# Sheet-watch.net
KiCad netlist of a schematic drawn in Altium Designer
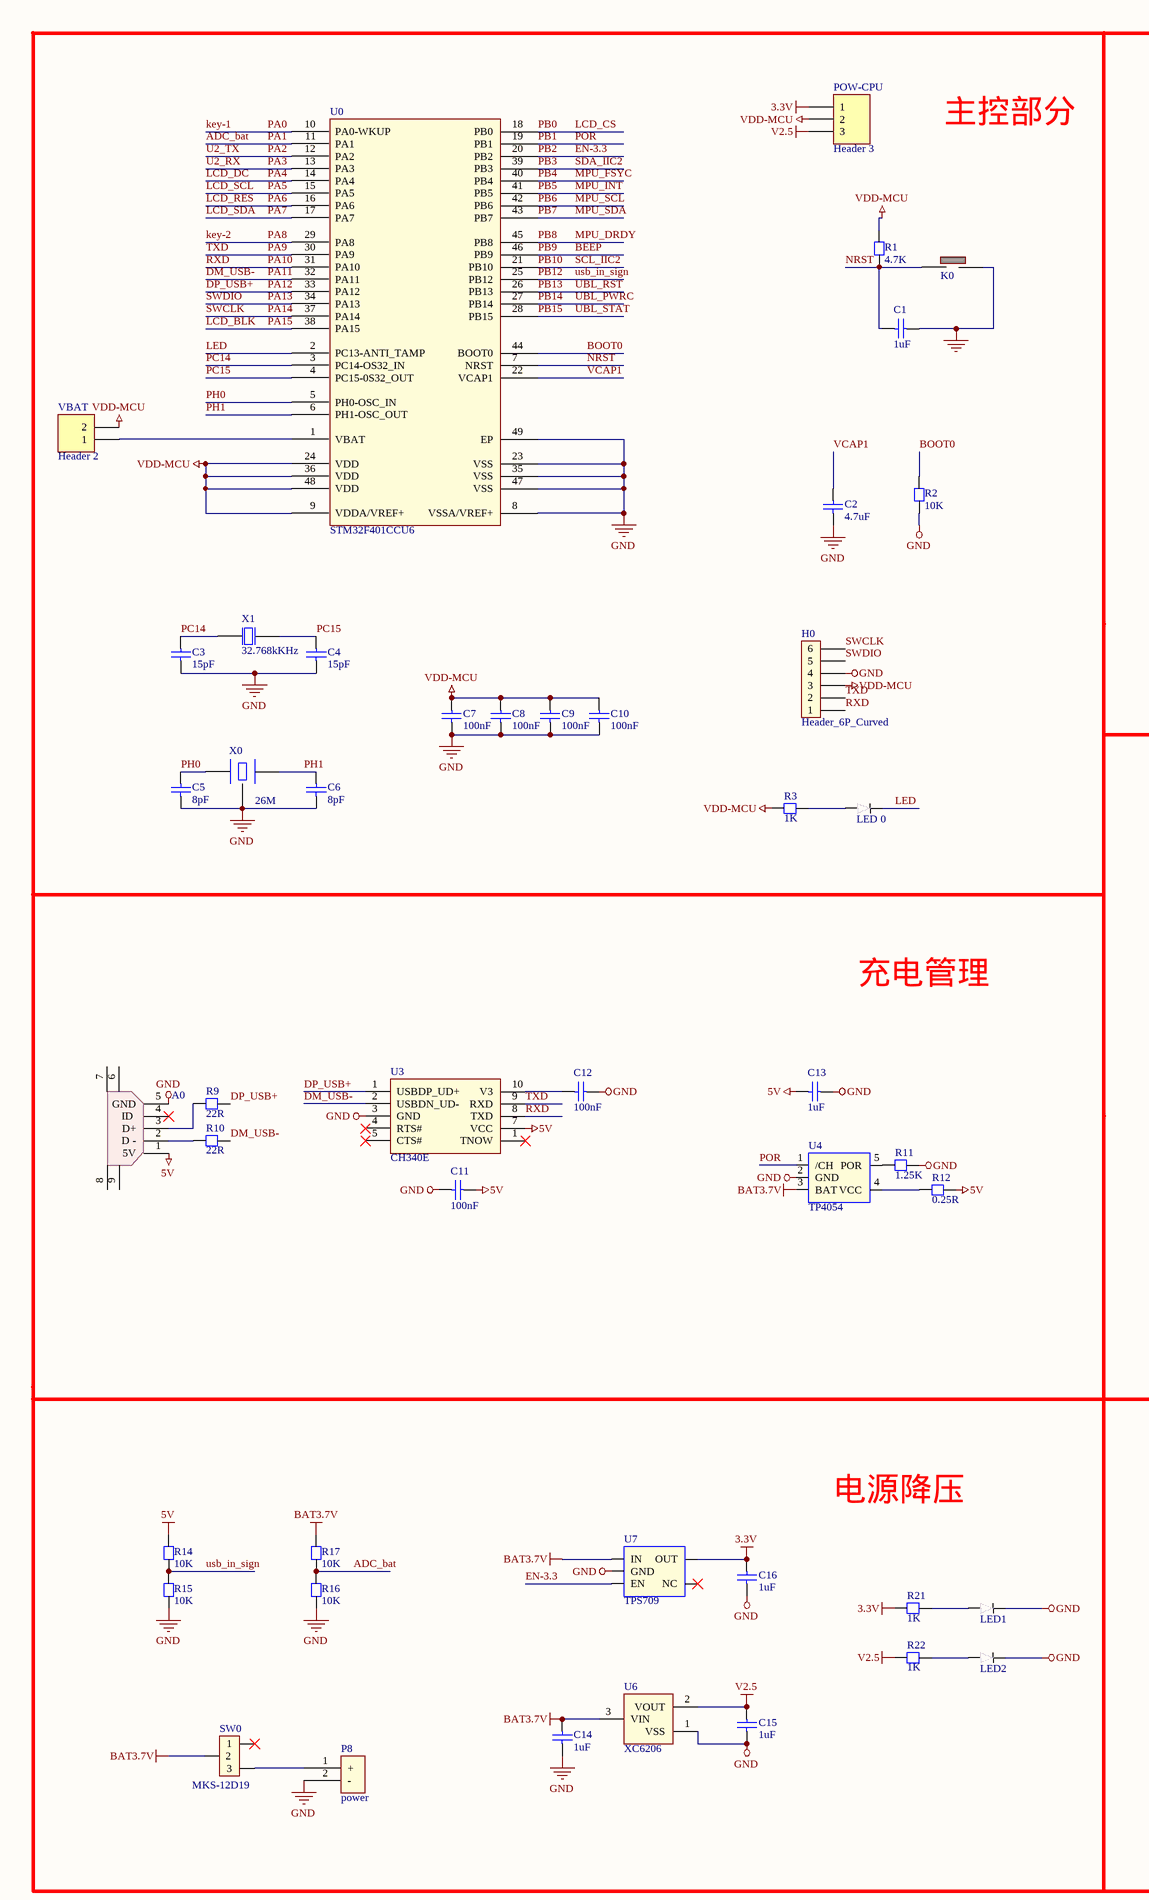
[diagram p0: Sheet-watch.SchDoc, left]
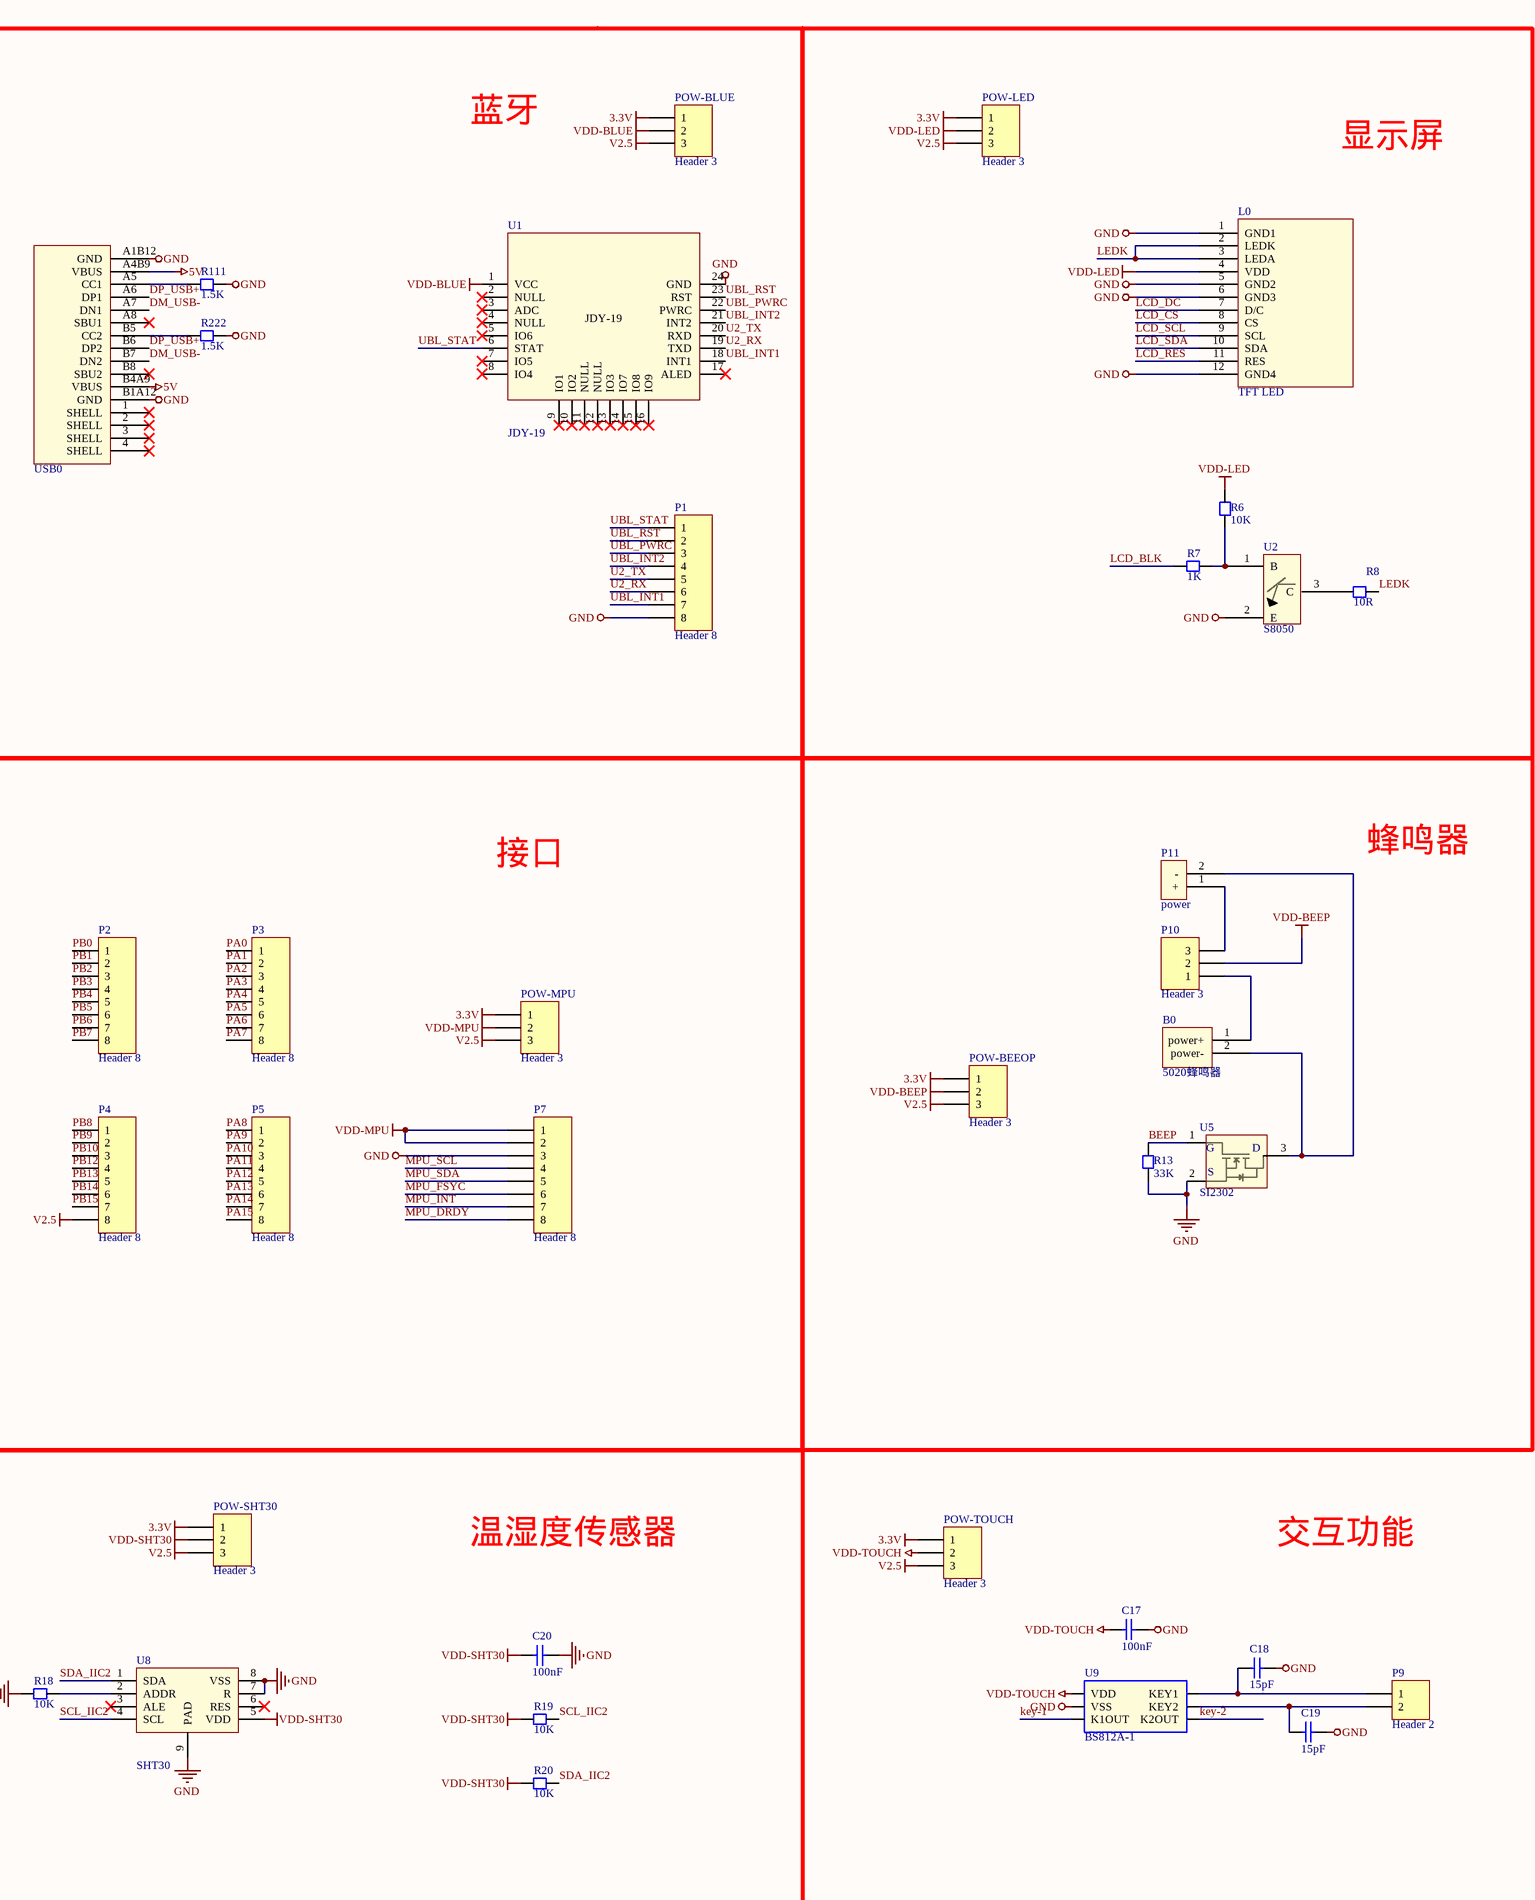
[diagram p1: Sheet-watch.SchDoc, right]

(export (version "E")
  (design (tool "Eeschema 10.0.6"))
  (components
    (comp (ref "A0")
      (value "Micro USB")
      (footprint "Micro usb AB")
      (description "迷你usb接口")
      (libsource (lib "tianxiaohua_Schlib") (part "Micro USB"))
    )
    (comp (ref "B0")
      (value "5020蜂鸣器")
      (footprint "5020蜂鸣器")
      (description "蜂鸣器，贴片封装，长宽5.2mm")
      (libsource (lib "tianxiaohua_Schlib") (part "5020蜂鸣器"))
    )
    (comp (ref "C1")
      (value "1uF")
      (footprint "CC1608-0603")
      (description "电容")
      (fields (field (name "PUBLISHER") "Altium Limited"))
      (libsource (lib "tianxiaohua_Schlib") (part "Cap Chip 0603"))
    )
    (comp (ref "C2")
      (value "4.7uF")
      (footprint "CC1608-0603")
      (description "电容")
      (fields (field (name "PUBLISHER") "Altium Limited"))
      (libsource (lib "tianxiaohua_Schlib") (part "Cap Chip 0603"))
    )
    (comp (ref "C3")
      (value "15pF")
      (footprint "CC1608-0603")
      (description "电容")
      (fields (field (name "PUBLISHER") "Altium Limited"))
      (libsource (lib "tianxiaohua_Schlib") (part "Cap Chip 0603"))
    )
    (comp (ref "C4")
      (value "15pF")
      (footprint "CC1608-0603")
      (description "电容")
      (fields (field (name "PUBLISHER") "Altium Limited"))
      (libsource (lib "tianxiaohua_Schlib") (part "Cap Chip 0603"))
    )
    (comp (ref "C5")
      (value "8pF")
      (footprint "CC1608-0603")
      (description "电容")
      (fields (field (name "PUBLISHER") "Altium Limited"))
      (libsource (lib "tianxiaohua_Schlib") (part "Cap Chip 0603"))
    )
    (comp (ref "C6")
      (value "8pF")
      (footprint "CC1608-0603")
      (description "电容")
      (fields (field (name "PUBLISHER") "Altium Limited"))
      (libsource (lib "tianxiaohua_Schlib") (part "Cap Chip 0603"))
    )
    (comp (ref "C7")
      (value "100nF")
      (footprint "CC1608-0603")
      (description "电容")
      (fields (field (name "PUBLISHER") "Altium Limited"))
      (libsource (lib "tianxiaohua_Schlib") (part "Cap Chip 0603"))
    )
    (comp (ref "C8")
      (value "100nF")
      (footprint "CC1608-0603")
      (description "电容")
      (fields (field (name "PUBLISHER") "Altium Limited"))
      (libsource (lib "tianxiaohua_Schlib") (part "Cap Chip 0603"))
    )
    (comp (ref "C9")
      (value "100nF")
      (footprint "CC1608-0603")
      (description "电容")
      (fields (field (name "PUBLISHER") "Altium Limited"))
      (libsource (lib "tianxiaohua_Schlib") (part "Cap Chip 0603"))
    )
    (comp (ref "C10")
      (value "100nF")
      (footprint "CC1608-0603")
      (description "电容")
      (fields (field (name "PUBLISHER") "Altium Limited"))
      (libsource (lib "tianxiaohua_Schlib") (part "Cap Chip 0603"))
    )
    (comp (ref "C11")
      (value "100nF")
      (footprint "CC1608-0603")
      (description "电容")
      (fields (field (name "PUBLISHER") "Altium Limited"))
      (libsource (lib "tianxiaohua_Schlib") (part "Cap Chip 0603"))
    )
    (comp (ref "C12")
      (value "100nF")
      (footprint "CC1608-0603")
      (description "电容")
      (fields (field (name "PUBLISHER") "Altium Limited"))
      (libsource (lib "tianxiaohua_Schlib") (part "Cap Chip 0603"))
    )
    (comp (ref "C13")
      (value "1uF")
      (footprint "CC1608-0603")
      (description "电容")
      (fields (field (name "PUBLISHER") "Altium Limited"))
      (libsource (lib "tianxiaohua_Schlib") (part "Cap Chip 0603"))
    )
    (comp (ref "C14")
      (value "1uF")
      (footprint "CC1608-0603")
      (description "电容")
      (fields (field (name "PUBLISHER") "Altium Limited"))
      (libsource (lib "tianxiaohua_Schlib") (part "Cap Chip 0603"))
    )
    (comp (ref "C15")
      (value "1uF")
      (footprint "CC1608-0603")
      (description "电容")
      (fields (field (name "PUBLISHER") "Altium Limited"))
      (libsource (lib "tianxiaohua_Schlib") (part "Cap Chip 0603"))
    )
    (comp (ref "C16")
      (value "1uF")
      (footprint "CC1608-0603")
      (description "电容")
      (fields (field (name "PUBLISHER") "Altium Limited"))
      (libsource (lib "tianxiaohua_Schlib") (part "Cap Chip 0603"))
    )
    (comp (ref "C17")
      (value "100nF")
      (footprint "CC1608-0603")
      (description "电容")
      (fields (field (name "PUBLISHER") "Altium Limited"))
      (libsource (lib "tianxiaohua_Schlib") (part "Cap Chip 0603"))
    )
    (comp (ref "C18")
      (value "15pF")
      (footprint "CC1608-0603")
      (description "电容")
      (fields (field (name "PUBLISHER") "Altium Limited"))
      (libsource (lib "tianxiaohua_Schlib") (part "Cap Chip 0603"))
    )
    (comp (ref "C19")
      (value "15pF")
      (footprint "CC1608-0603")
      (description "电容")
      (fields (field (name "PUBLISHER") "Altium Limited"))
      (libsource (lib "tianxiaohua_Schlib") (part "Cap Chip 0603"))
    )
    (comp (ref "C20")
      (value "100nF")
      (footprint "CC1608-0603")
      (description "电容")
      (fields (field (name "PUBLISHER") "Altium Limited"))
      (libsource (lib "tianxiaohua_Schlib") (part "Cap Chip 0603"))
    )
    (comp (ref "H0")
      (value "Header_6P_Curved")
      (footprint "Header_2_54_6PW")
      (description "弯的6P排针")
      (libsource (lib "tianxiaohua_Schlib") (part "Header_6P_Curved"))
    )
    (comp (ref "K0")
      (value "KEY 3*4")
      (footprint "KEY 3*4")
      (libsource (lib "tianxiaohua_Schlib") (part "KEY 3*4"))
    )
    (comp (ref "L0")
      (value "TFT LED")
      (footprint "LCD-1.3-(2)")
      (description "1.3寸显示屏幕")
      (libsource (lib "tianxiaohua_Schlib") (part "LCD-IPSscreen-1.3"))
    )
    (comp (ref "LED 0")
      (value "LED 0603")
      (footprint "LED 0603")
      (libsource (lib "tianxiaohua_Schlib") (part "LED 0603"))
    )
    (comp (ref "LED1")
      (value "LED 0603")
      (footprint "LED 0603")
      (libsource (lib "tianxiaohua_Schlib") (part "LED 0603"))
    )
    (comp (ref "LED2")
      (value "LED 0603")
      (footprint "LED 0603")
      (libsource (lib "tianxiaohua_Schlib") (part "LED 0603"))
    )
    (comp (ref "P1")
      (value "Header 8")
      (footprint "HDR1X8")
      (description "Header, 8-Pin")
      (fields (field (name "PUBLISHER") "Altium Limited"))
      (libsource (lib "EButterflyIntegratedLibrary") (part "Header 8"))
    )
    (comp (ref "P2")
      (value "Header 8")
      (footprint "HDR1X8")
      (description "Header, 8-Pin")
      (fields (field (name "PUBLISHER") "Altium Limited"))
      (libsource (lib "EButterflyIntegratedLibrary") (part "Header 8"))
    )
    (comp (ref "P3")
      (value "Header 8")
      (footprint "HDR1X8")
      (description "Header, 8-Pin")
      (fields (field (name "PUBLISHER") "Altium Limited"))
      (libsource (lib "EButterflyIntegratedLibrary") (part "Header 8"))
    )
    (comp (ref "P4")
      (value "Header 8")
      (footprint "HDR1X8")
      (description "Header, 8-Pin")
      (fields (field (name "PUBLISHER") "Altium Limited"))
      (libsource (lib "EButterflyIntegratedLibrary") (part "Header 8"))
    )
    (comp (ref "P5")
      (value "Header 8")
      (footprint "HDR1X8")
      (description "Header, 8-Pin")
      (fields (field (name "PUBLISHER") "Altium Limited"))
      (libsource (lib "EButterflyIntegratedLibrary") (part "Header 8"))
    )
    (comp (ref "P7")
      (value "Header 8")
      (footprint "HDR1X8")
      (description "Header, 8-Pin")
      (fields (field (name "PUBLISHER") "Altium Limited"))
      (libsource (lib "EButterflyIntegratedLibrary") (part "Header 8"))
    )
    (comp (ref "P8")
      (value "power")
      (footprint "POWER-3.7V")
      (libsource (lib "tianxiaohua_Schlib") (part "power"))
    )
    (comp (ref "P9")
      (value "Header 2")
      (footprint "HDR1X2")
      (description "Header, 2-Pin")
      (fields (field (name "PUBLISHER") "Altium Limited"))
      (libsource (lib "EButterflyIntegratedLibrary") (part "Header 2"))
    )
    (comp (ref "P10")
      (value "Header 3")
      (footprint "HDR1X3")
      (description "Header, 3-Pin")
      (fields (field (name "PUBLISHER") "Altium Limited"))
      (libsource (lib "EButterflyIntegratedLibrary") (part "Header 3"))
    )
    (comp (ref "P11") (value "power") (footprint "POWER-3.7V") (libsource (lib "") (part "power_1")))
    (comp (ref "POW-BEEOP")
      (value "Header 3")
      (footprint "HDR1X3")
      (description "Header, 3-Pin")
      (fields (field (name "PUBLISHER") "Altium Limited"))
      (libsource (lib "") (part "Header 3_1"))
    )
    (comp (ref "POW-BLUE")
      (value "Header 3")
      (footprint "HDR1X3")
      (description "Header, 3-Pin")
      (fields (field (name "PUBLISHER") "Altium Limited"))
      (libsource (lib "") (part "Header 3_1"))
    )
    (comp (ref "POW-CPU")
      (value "Header 3")
      (footprint "HDR1X3")
      (description "Header, 3-Pin")
      (fields (field (name "PUBLISHER") "Altium Limited"))
      (libsource (lib "") (part "Header 3_1"))
    )
    (comp (ref "POW-LED")
      (value "Header 3")
      (footprint "HDR1X3")
      (description "Header, 3-Pin")
      (fields (field (name "PUBLISHER") "Altium Limited"))
      (libsource (lib "") (part "Header 3_1"))
    )
    (comp (ref "POW-MPU")
      (value "Header 3")
      (footprint "HDR1X3")
      (description "Header, 3-Pin")
      (fields (field (name "PUBLISHER") "Altium Limited"))
      (libsource (lib "") (part "Header 3_1"))
    )
    (comp (ref "POW-SHT30")
      (value "Header 3")
      (footprint "HDR1X3")
      (description "Header, 3-Pin")
      (fields (field (name "PUBLISHER") "Altium Limited"))
      (libsource (lib "") (part "Header 3_1"))
    )
    (comp (ref "POW-TOUCH")
      (value "Header 3")
      (footprint "HDR1X3")
      (description "Header, 3-Pin")
      (fields (field (name "PUBLISHER") "Altium Limited"))
      (libsource (lib "") (part "Header 3_1"))
    )
    (comp (ref "R1")
      (value "4.7K")
      (footprint "CR1608-0603")
      (description "电阻")
      (fields (field (name "PUBLISHER") "Altium Limited"))
      (libsource (lib "tianxiaohua_Schlib") (part "Resistor Chip 0603"))
    )
    (comp (ref "R2")
      (value "10K")
      (footprint "CR1608-0603")
      (description "电阻")
      (fields (field (name "PUBLISHER") "Altium Limited"))
      (libsource (lib "") (part "Resistor Chip 0603_3"))
    )
    (comp (ref "R3")
      (value "1K")
      (footprint "CR1608-0603")
      (description "电阻")
      (fields (field (name "PUBLISHER") "Altium Limited"))
      (libsource (lib "") (part "Resistor Chip 0603_2"))
    )
    (comp (ref "R6")
      (value "10K")
      (footprint "CR1608-0603")
      (description "电阻")
      (fields (field (name "PUBLISHER") "Altium Limited"))
      (libsource (lib "") (part "Resistor Chip 0603_3"))
    )
    (comp (ref "R7")
      (value "1K")
      (footprint "CR1608-0603")
      (description "电阻")
      (fields (field (name "PUBLISHER") "Altium Limited"))
      (libsource (lib "") (part "Resistor Chip 0603_2"))
    )
    (comp (ref "R8")
      (value "10R")
      (footprint "CR1608-0603")
      (description "电阻")
      (fields (field (name "PUBLISHER") "Altium Limited"))
      (libsource (lib "") (part "Resistor Chip 0603_2"))
    )
    (comp (ref "R9")
      (value "22R")
      (footprint "CR1608-0603")
      (description "电阻")
      (fields (field (name "PUBLISHER") "Altium Limited"))
      (libsource (lib "") (part "Resistor Chip 0603_2"))
    )
    (comp (ref "R10")
      (value "22R")
      (footprint "CR1608-0603")
      (description "电阻")
      (fields (field (name "PUBLISHER") "Altium Limited"))
      (libsource (lib "") (part "Resistor Chip 0603_2"))
    )
    (comp (ref "R11")
      (value "1.25K")
      (footprint "CR1608-0603")
      (description "电阻")
      (fields (field (name "PUBLISHER") "Altium Limited"))
      (libsource (lib "") (part "Resistor Chip 0603_2"))
    )
    (comp (ref "R12")
      (value "0.25R")
      (footprint "CR1608-0603")
      (description "电阻")
      (fields (field (name "PUBLISHER") "Altium Limited"))
      (libsource (lib "") (part "Resistor Chip 0603_2"))
    )
    (comp (ref "R13")
      (value "33K")
      (footprint "CR1608-0603")
      (description "电阻")
      (fields (field (name "PUBLISHER") "Altium Limited"))
      (libsource (lib "") (part "Resistor Chip 0603_3"))
    )
    (comp (ref "R14")
      (value "10K")
      (footprint "CR1608-0603")
      (description "电阻")
      (fields (field (name "PUBLISHER") "Altium Limited"))
      (libsource (lib "") (part "Resistor Chip 0603_3"))
    )
    (comp (ref "R15")
      (value "10K")
      (footprint "CR1608-0603")
      (description "电阻")
      (fields (field (name "PUBLISHER") "Altium Limited"))
      (libsource (lib "") (part "Resistor Chip 0603_3"))
    )
    (comp (ref "R16")
      (value "10K")
      (footprint "CR1608-0603")
      (description "电阻")
      (fields (field (name "PUBLISHER") "Altium Limited"))
      (libsource (lib "tianxiaohua_Schlib") (part "Resistor Chip 0603"))
    )
    (comp (ref "R17")
      (value "10K")
      (footprint "CR1608-0603")
      (description "电阻")
      (fields (field (name "PUBLISHER") "Altium Limited"))
      (libsource (lib "tianxiaohua_Schlib") (part "Resistor Chip 0603"))
    )
    (comp (ref "R18")
      (value "10K")
      (footprint "CR1608-0603")
      (description "电阻")
      (fields (field (name "PUBLISHER") "Altium Limited"))
      (libsource (lib "") (part "Resistor Chip 0603_1"))
    )
    (comp (ref "R19")
      (value "10K")
      (footprint "CR1608-0603")
      (description "电阻")
      (fields (field (name "PUBLISHER") "Altium Limited"))
      (libsource (lib "") (part "Resistor Chip 0603_1"))
    )
    (comp (ref "R20")
      (value "10K")
      (footprint "CR1608-0603")
      (description "电阻")
      (fields (field (name "PUBLISHER") "Altium Limited"))
      (libsource (lib "") (part "Resistor Chip 0603_1"))
    )
    (comp (ref "R21")
      (value "1K")
      (footprint "CR1608-0603")
      (description "电阻")
      (fields (field (name "PUBLISHER") "Altium Limited"))
      (libsource (lib "") (part "Resistor Chip 0603_2"))
    )
    (comp (ref "R22")
      (value "1K")
      (footprint "CR1608-0603")
      (description "电阻")
      (fields (field (name "PUBLISHER") "Altium Limited"))
      (libsource (lib "") (part "Resistor Chip 0603_2"))
    )
    (comp (ref "R111")
      (value "1.5K")
      (footprint "CR1608-0603")
      (description "电阻")
      (fields (field (name "PUBLISHER") "Altium Limited"))
      (libsource (lib "") (part "Resistor Chip 0603_2"))
    )
    (comp (ref "R222")
      (value "1.5K")
      (footprint "CR1608-0603")
      (description "电阻")
      (fields (field (name "PUBLISHER") "Altium Limited"))
      (libsource (lib "") (part "Resistor Chip 0603_2"))
    )
    (comp (ref "SW0")
      (value "MKS-12D19")
      (footprint "SW  MSK-02")
      (libsource (lib "tianxiaohua_Schlib") (part "sw-MSK-12D19"))
    )
    (comp (ref "U0")
      (value "STM32F401CCU6")
      (footprint "STM32-UFQFPN48_N")
      (description "stm32单片机 主频100MHz")
      (libsource (lib "tianxiaohua_Schlib") (part "stm32F411CEU6"))
    )
    (comp (ref "U1")
      (value "JDY-19")
      (footprint "JDY-19")
      (description "超低功耗蓝牙 4.2 BLE 模块")
      (libsource (lib "tianxiaohua_Schlib") (part "JDY-19"))
    )
    (comp (ref "U2")
      (value "S8050")
      (footprint "SOT-23 SI2302")
      (description "三极管放大管 NPN型三极管 大电流300ma")
      (libsource (lib "tianxiaohua_Schlib") (part "S8050"))
    )
    (comp (ref "U3")
      (value "CH340E")
      (footprint "MSOP-10")
      (description "usd转串口芯片 MSOP10封装")
      (libsource (lib "tianxiaohua_Schlib") (part "CH340E"))
    )
    (comp (ref "U4")
      (value "TP4054")
      (footprint "SOT23-5")
      (description "迷你充电IC SOT-23-5")
      (libsource (lib "tianxiaohua_Schlib") (part "TP4054"))
    )
    (comp (ref "U5")
      (value "SI2302")
      (footprint "SOT-23 SI2302")
      (description "NMOS场效应MOS管 SOT-23")
      (libsource (lib "tianxiaohua_Schlib") (part "SI2302"))
    )
    (comp (ref "U6")
      (value "XC6206")
      (footprint "SOT-23 SI2302")
      (description "2.5V降压IC SOT-23封装")
      (libsource (lib "tianxiaohua_Schlib") (part "XC6206"))
    )
    (comp (ref "U7")
      (value "TPS709")
      (footprint "SOT23-5")
      (description "3.3V降压IC SOT23-5封装 最大输出150ma电流")
      (libsource (lib "tianxiaohua_Schlib") (part "TPS709"))
    )
    (comp (ref "U8")
      (value "SHT30")
      (footprint "SHT3X-DIS")
      (description "温湿度传感器")
      (libsource (lib "tianxiaohua_Schlib") (part "SHT30"))
    )
    (comp (ref "U9")
      (value "BS812A-1")
      (footprint "SOT23-6")
      (description "触摸按键 两路 SOP23-6封装极简电路")
      (libsource (lib "tianxiaohua_Schlib") (part "BS812A-1"))
    )
    (comp (ref "USB0")
      (value "Tpye-c 16P")
      (footprint "TYPE-C 16P")
      (description "16P 封装的TYPE -c接口 4固定插脚 双向")
      (libsource (lib "tianxiaohua_Schlib") (part "Tpye-c 16P"))
    )
    (comp (ref "VBAT")
      (value "Header 2")
      (footprint "HDR1X2")
      (description "Header, 2-Pin")
      (fields (field (name "PUBLISHER") "Altium Limited"))
      (libsource (lib "") (part "Header 2_1"))
    )
    (comp (ref "X0")
      (value "26M")
      (footprint "XTAL-3225")
      (description "3225封装的晶振")
      (libsource (lib "tianxiaohua_Schlib") (part "XTAL 3225"))
    )
    (comp (ref "X1")
      (value "32.768kKHz")
      (footprint "XTAL-3215")
      (description "3215封装的时钟晶振")
      (libsource (lib "tianxiaohua_Schlib") (part "XTAL 3215 32.768kKHz"))
    )
  )
  (nets
    (net (code "1") (name "/ADC_bat") (class "Default")
      (node (ref "P3") (pin "2") (pinfunction "2_2") (pintype "passive"))
      (node (ref "R16") (pin "2") (pinfunction "2_2") (pintype "passive"))
      (node (ref "R17") (pin "1") (pinfunction "1_1") (pintype "passive"))
      (node (ref "U0") (pin "11") (pinfunction "PA1_11") (pintype "passive"))
    )
    (net (code "2") (name "/BEEP") (class "Default")
      (node (ref "P4") (pin "2") (pinfunction "2_2") (pintype "passive"))
      (node (ref "R13") (pin "1") (pinfunction "1_1") (pintype "passive"))
      (node (ref "U0") (pin "46") (pinfunction "PB9_46") (pintype "passive"))
      (node (ref "U5") (pin "1") (pinfunction "GATE_1") (pintype "passive"))
    )
    (net (code "3") (name "/BOOT0") (class "Default")
      (node (ref "R2") (pin "1") (pinfunction "1_1") (pintype "passive"))
      (node (ref "U0") (pin "44") (pinfunction "BOOT0_44") (pintype "passive"))
    )
    (net (code "4") (name "/DM_USB-") (class "Default")
      (node (ref "P5") (pin "4") (pinfunction "4_4") (pintype "passive"))
      (node (ref "R10") (pin "1") (pinfunction "1_1") (pintype "passive"))
      (node (ref "U0") (pin "32") (pinfunction "PA11_32") (pintype "passive"))
      (node (ref "U3") (pin "2") (pinfunction "USBDN_UD-_2") (pintype "passive"))
      (node (ref "USB0") (pin "A7") (pinfunction "DN1_A7") (pintype "power_in"))
      (node (ref "USB0") (pin "B7") (pinfunction "DN2_B7") (pintype "power_in"))
    )
    (net (code "5") (name "/DP_USB+") (class "Default")
      (node (ref "P5") (pin "5") (pinfunction "5_5") (pintype "passive"))
      (node (ref "R9") (pin "1") (pinfunction "1_1") (pintype "passive"))
      (node (ref "U0") (pin "33") (pinfunction "PA12_33") (pintype "passive"))
      (node (ref "U3") (pin "1") (pinfunction "USBDP_UD+_1") (pintype "passive"))
      (node (ref "USB0") (pin "A6") (pinfunction "DP1_A6") (pintype "power_in"))
      (node (ref "USB0") (pin "B6") (pinfunction "DP2_B6") (pintype "power_in"))
    )
    (net (code "6") (name "/EN-3.3") (class "Default")
      (node (ref "P2") (pin "3") (pinfunction "3_3") (pintype "passive"))
      (node (ref "U0") (pin "20") (pinfunction "PB2_20") (pintype "passive"))
      (node (ref "U7") (pin "3") (pinfunction "EN_3") (pintype "passive"))
    )
    (net (code "7") (name "/LCD_BLK") (class "Default")
      (node (ref "P5") (pin "8") (pinfunction "8_8") (pintype "passive"))
      (node (ref "R7") (pin "2") (pinfunction "2_2") (pintype "passive"))
      (node (ref "U0") (pin "38") (pinfunction "PA15_38") (pintype "passive"))
    )
    (net (code "8") (name "/LCD_CS") (class "Default")
      (node (ref "L0") (pin "8") (pinfunction "CS_8") (pintype "passive"))
      (node (ref "P2") (pin "1") (pinfunction "1_1") (pintype "passive"))
      (node (ref "U0") (pin "18") (pinfunction "PB0_18") (pintype "passive"))
    )
    (net (code "9") (name "/LCD_DC") (class "Default")
      (node (ref "L0") (pin "7") (pinfunction "D/C_7") (pintype "passive"))
      (node (ref "P3") (pin "5") (pinfunction "5_5") (pintype "passive"))
      (node (ref "U0") (pin "14") (pinfunction "PA4_14") (pintype "passive"))
    )
    (net (code "10") (name "/LCD_RES") (class "Default")
      (node (ref "L0") (pin "11") (pinfunction "RES_11") (pintype "passive"))
      (node (ref "P3") (pin "7") (pinfunction "7_7") (pintype "passive"))
      (node (ref "U0") (pin "16") (pinfunction "PA6_16") (pintype "passive"))
    )
    (net (code "11") (name "/LCD_SCL") (class "Default")
      (node (ref "L0") (pin "9") (pinfunction "SCL_9") (pintype "passive"))
      (node (ref "P3") (pin "6") (pinfunction "6_6") (pintype "passive"))
      (node (ref "U0") (pin "15") (pinfunction "PA5_15") (pintype "passive"))
    )
    (net (code "12") (name "/LCD_SDA") (class "Default")
      (node (ref "L0") (pin "10") (pinfunction "SDA_10") (pintype "passive"))
      (node (ref "P3") (pin "8") (pinfunction "8_8") (pintype "passive"))
      (node (ref "U0") (pin "17") (pinfunction "PA7_17") (pintype "passive"))
    )
    (net (code "13") (name "/LED") (class "Default")
      (node (ref "LED 0") (pin "2") (pinfunction "2_2") (pintype "passive"))
      (node (ref "U0") (pin "2") (pinfunction "PC13-ANTI_TAMP_2") (pintype "passive"))
    )
    (net (code "14") (name "/LEDK") (class "Default")
      (node (ref "L0") (pin "2") (pinfunction "LEDK_2") (pintype "passive"))
      (node (ref "L0") (pin "3") (pinfunction "LEDA_3") (pintype "passive"))
      (node (ref "R8") (pin "1") (pinfunction "1_1") (pintype "passive"))
    )
    (net (code "15") (name "/MPU_DRDY") (class "Default")
      (node (ref "P4") (pin "1") (pinfunction "1_1") (pintype "passive"))
      (node (ref "P7") (pin "8") (pinfunction "8_8") (pintype "passive"))
      (node (ref "U0") (pin "45") (pinfunction "PB8_45") (pintype "passive"))
    )
    (net (code "16") (name "/MPU_FSYC") (class "Default")
      (node (ref "P2") (pin "5") (pinfunction "5_5") (pintype "passive"))
      (node (ref "P7") (pin "6") (pinfunction "6_6") (pintype "passive"))
      (node (ref "U0") (pin "40") (pinfunction "PB4_40") (pintype "passive"))
    )
    (net (code "17") (name "/MPU_INT") (class "Default")
      (node (ref "P2") (pin "6") (pinfunction "6_6") (pintype "passive"))
      (node (ref "P7") (pin "7") (pinfunction "7_7") (pintype "passive"))
      (node (ref "U0") (pin "41") (pinfunction "PB5_41") (pintype "passive"))
    )
    (net (code "18") (name "/MPU_SCL") (class "Default")
      (node (ref "P2") (pin "7") (pinfunction "7_7") (pintype "passive"))
      (node (ref "P7") (pin "4") (pinfunction "4_4") (pintype "passive"))
      (node (ref "U0") (pin "42") (pinfunction "PB6_42") (pintype "passive"))
    )
    (net (code "19") (name "/MPU_SDA") (class "Default")
      (node (ref "P2") (pin "8") (pinfunction "8_8") (pintype "passive"))
      (node (ref "P7") (pin "5") (pinfunction "5_5") (pintype "passive"))
      (node (ref "U0") (pin "43") (pinfunction "PB7_43") (pintype "passive"))
    )
    (net (code "20") (name "/NRST") (class "Default")
      (node (ref "C1") (pin "2") (pinfunction "2_2") (pintype "passive"))
      (node (ref "K0") (pin "1") (pinfunction "1_1") (pintype "passive"))
      (node (ref "R1") (pin "1") (pinfunction "1_1") (pintype "passive"))
      (node (ref "U0") (pin "7") (pinfunction "NRST_7") (pintype "passive"))
    )
    (net (code "21") (name "/PA0") (class "Default")
      (node (ref "P3") (pin "1") (pinfunction "1_1") (pintype "passive"))
      (node (ref "U0") (pin "10") (pinfunction "PA0-WKUP_10") (pintype "passive"))
      (node (ref "U9") (pin "3") (pinfunction "K1OUT_3") (pintype "passive"))
    )
    (net (code "22") (name "/PA2") (class "Default")
      (node (ref "P1") (pin "5") (pinfunction "5_5") (pintype "passive"))
      (node (ref "P3") (pin "3") (pinfunction "3_3") (pintype "passive"))
      (node (ref "U0") (pin "12") (pinfunction "PA2_12") (pintype "passive"))
      (node (ref "U1") (pin "20") (pinfunction "RXD_20") (pintype "passive"))
    )
    (net (code "23") (name "/PA3") (class "Default")
      (node (ref "P1") (pin "6") (pinfunction "6_6") (pintype "passive"))
      (node (ref "P3") (pin "4") (pinfunction "4_4") (pintype "passive"))
      (node (ref "U0") (pin "13") (pinfunction "PA3_13") (pintype "passive"))
      (node (ref "U1") (pin "19") (pinfunction "TXD_19") (pintype "passive"))
    )
    (net (code "24") (name "/PA8") (class "Default")
      (node (ref "P5") (pin "1") (pinfunction "1_1") (pintype "passive"))
      (node (ref "U0") (pin "29") (pinfunction "PA8_29") (pintype "passive"))
      (node (ref "U9") (pin "4") (pinfunction "K2OUT_4") (pintype "passive"))
    )
    (net (code "25") (name "/PA9") (class "Default")
      (node (ref "H0") (pin "2") (pinfunction "2_2") (pintype "passive"))
      (node (ref "P5") (pin "2") (pinfunction "2_2") (pintype "passive"))
      (node (ref "U0") (pin "30") (pinfunction "PA9_30") (pintype "passive"))
      (node (ref "U3") (pin "9") (pinfunction "RXD_9") (pintype "passive"))
    )
    (net (code "26") (name "/PA10") (class "Default")
      (node (ref "H0") (pin "1") (pinfunction "1_1") (pintype "passive"))
      (node (ref "P5") (pin "3") (pinfunction "3_3") (pintype "passive"))
      (node (ref "U0") (pin "31") (pinfunction "PA10_31") (pintype "passive"))
      (node (ref "U3") (pin "8") (pinfunction "TXD_8") (pintype "passive"))
    )
    (net (code "27") (name "/PA13") (class "Default")
      (node (ref "H0") (pin "5") (pinfunction "5_5") (pintype "passive"))
      (node (ref "P5") (pin "6") (pinfunction "6_6") (pintype "passive"))
      (node (ref "U0") (pin "34") (pinfunction "PA13_34") (pintype "passive"))
    )
    (net (code "28") (name "/PA14") (class "Default")
      (node (ref "H0") (pin "6") (pinfunction "6_6") (pintype "passive"))
      (node (ref "P5") (pin "7") (pinfunction "7_7") (pintype "passive"))
      (node (ref "U0") (pin "37") (pinfunction "PA14_37") (pintype "passive"))
    )
    (net (code "29") (name "/PB1") (class "Default")
      (node (ref "P2") (pin "2") (pinfunction "2_2") (pintype "passive"))
      (node (ref "U0") (pin "19") (pinfunction "PB1_19") (pintype "passive"))
      (node (ref "U4") (pin "1") (pinfunction "/CH_1") (pintype "passive"))
    )
    (net (code "30") (name "/PB3") (class "Default")
      (node (ref "P2") (pin "4") (pinfunction "4_4") (pintype "passive"))
      (node (ref "R20") (pin "2") (pinfunction "2_2") (pintype "passive"))
      (node (ref "U0") (pin "39") (pinfunction "PB3_39") (pintype "passive"))
      (node (ref "U8") (pin "1") (pinfunction "SDA_1") (pintype "passive"))
    )
    (net (code "31") (name "/PB10") (class "Default")
      (node (ref "P4") (pin "3") (pinfunction "3_3") (pintype "passive"))
      (node (ref "R19") (pin "2") (pinfunction "2_2") (pintype "passive"))
      (node (ref "U0") (pin "21") (pinfunction "PB10_21") (pintype "passive"))
      (node (ref "U8") (pin "4") (pinfunction "SCL_4") (pintype "passive"))
    )
    (net (code "32") (name "/PB12") (class "Default")
      (node (ref "P4") (pin "4") (pinfunction "4_4") (pintype "passive"))
      (node (ref "R14") (pin "2") (pinfunction "2_2") (pintype "passive"))
      (node (ref "R15") (pin "1") (pinfunction "1_1") (pintype "passive"))
      (node (ref "U0") (pin "25") (pinfunction "PB12_25") (pintype "passive"))
    )
    (net (code "33") (name "/PB13") (class "Default")
      (node (ref "P1") (pin "2") (pinfunction "2_2") (pintype "passive"))
      (node (ref "P4") (pin "5") (pinfunction "5_5") (pintype "passive"))
      (node (ref "U0") (pin "26") (pinfunction "PB13_26") (pintype "passive"))
      (node (ref "U1") (pin "23") (pinfunction "RST_23") (pintype "passive"))
    )
    (net (code "34") (name "/PB14") (class "Default")
      (node (ref "P1") (pin "3") (pinfunction "3_3") (pintype "passive"))
      (node (ref "P4") (pin "6") (pinfunction "6_6") (pintype "passive"))
      (node (ref "U0") (pin "27") (pinfunction "PB14_27") (pintype "passive"))
      (node (ref "U1") (pin "22") (pinfunction "PWRC_22") (pintype "passive"))
    )
    (net (code "35") (name "/PB15") (class "Default")
      (node (ref "P1") (pin "1") (pinfunction "1_1") (pintype "passive"))
      (node (ref "P4") (pin "7") (pinfunction "7_7") (pintype "passive"))
      (node (ref "U0") (pin "28") (pinfunction "PB15_28") (pintype "passive"))
      (node (ref "U1") (pin "6") (pinfunction "STAT_6") (pintype "passive"))
    )
    (net (code "36") (name "/PC14") (class "Default")
      (node (ref "C3") (pin "2") (pinfunction "2_2") (pintype "passive"))
      (node (ref "U0") (pin "3") (pinfunction "PC14-OS32_IN_3") (pintype "passive"))
      (node (ref "X1") (pin "1") (pinfunction "OSC1_1") (pintype "passive"))
    )
    (net (code "37") (name "/PC15") (class "Default")
      (node (ref "C4") (pin "2") (pinfunction "2_2") (pintype "passive"))
      (node (ref "U0") (pin "4") (pinfunction "PC15-0S32_OUT_4") (pintype "passive"))
      (node (ref "X1") (pin "2") (pinfunction "OSC2_2") (pintype "passive"))
    )
    (net (code "38") (name "/PH0") (class "Default")
      (node (ref "C5") (pin "2") (pinfunction "2_2") (pintype "passive"))
      (node (ref "U0") (pin "5") (pinfunction "PH0-OSC_IN_5") (pintype "passive"))
      (node (ref "X0") (pin "1") (pinfunction "OSC1_1") (pintype "passive"))
    )
    (net (code "39") (name "/PH1") (class "Default")
      (node (ref "C6") (pin "2") (pinfunction "2_2") (pintype "passive"))
      (node (ref "U0") (pin "6") (pinfunction "PH1-OSC_OUT_6") (pintype "passive"))
      (node (ref "X0") (pin "3") (pinfunction "OSC2_3") (pintype "passive"))
    )
    (net (code "40") (name "/UBL_INT1") (class "Default")
      (node (ref "P1") (pin "7") (pinfunction "7_7") (pintype "passive"))
      (node (ref "U1") (pin "18") (pinfunction "INT1_18") (pintype "passive"))
    )
    (net (code "41") (name "/UBL_INT2") (class "Default")
      (node (ref "P1") (pin "4") (pinfunction "4_4") (pintype "passive"))
      (node (ref "U1") (pin "21") (pinfunction "INT2_21") (pintype "passive"))
    )
    (net (code "42") (name "/VCAP1") (class "Default")
      (node (ref "C2") (pin "2") (pinfunction "2_2") (pintype "passive"))
      (node (ref "U0") (pin "22") (pinfunction "VCAP1_22") (pintype "passive"))
    )
    (net (code "43") (name "3.3V") (class "Default")
      (node (ref "C16") (pin "2") (pinfunction "2_2") (pintype "passive"))
      (node (ref "POW-BEEOP") (pin "1") (pinfunction "1_1") (pintype "passive"))
      (node (ref "POW-BLUE") (pin "1") (pinfunction "1_1") (pintype "passive"))
      (node (ref "POW-CPU") (pin "1") (pinfunction "1_1") (pintype "passive"))
      (node (ref "POW-LED") (pin "1") (pinfunction "1_1") (pintype "passive"))
      (node (ref "POW-MPU") (pin "1") (pinfunction "1_1") (pintype "passive"))
      (node (ref "POW-SHT30") (pin "1") (pinfunction "1_1") (pintype "passive"))
      (node (ref "POW-TOUCH") (pin "1") (pinfunction "1_1") (pintype "passive"))
      (node (ref "R21") (pin "2") (pinfunction "2_2") (pintype "passive"))
      (node (ref "U7") (pin "5") (pinfunction "OUT_5") (pintype "passive"))
    )
    (net (code "44") (name "5V") (class "Default")
      (node (ref "A0") (pin "1") (pinfunction "5V_1") (pintype "passive"))
      (node (ref "C11") (pin "1") (pinfunction "1_1") (pintype "passive"))
      (node (ref "C13") (pin "2") (pinfunction "2_2") (pintype "passive"))
      (node (ref "R12") (pin "1") (pinfunction "1_1") (pintype "passive"))
      (node (ref "R14") (pin "1") (pinfunction "1_1") (pintype "passive"))
      (node (ref "U3") (pin "7") (pinfunction "VCC_7") (pintype "passive"))
      (node (ref "USB0") (pin "A4B9") (pinfunction "VBUS_A4B9") (pintype "power_in"))
      (node (ref "USB0") (pin "B4A9") (pinfunction "VBUS_B4A9") (pintype "power_in"))
    )
    (net (code "45") (name "BAT3.7V") (class "Default")
      (node (ref "C14") (pin "2") (pinfunction "2_2") (pintype "passive"))
      (node (ref "R17") (pin "2") (pinfunction "2_2") (pintype "passive"))
      (node (ref "SW0") (pin "2") (pinfunction "2_2") (pintype "passive"))
      (node (ref "U4") (pin "3") (pinfunction "BAT_3") (pintype "passive"))
      (node (ref "U6") (pin "3") (pinfunction "VIN_3") (pintype "passive"))
      (node (ref "U7") (pin "1") (pinfunction "IN_1") (pintype "passive"))
    )
    (net (code "46") (name "GND") (class "Default")
      (node (ref "A0") (pin "5") (pinfunction "GND_5") (pintype "passive"))
      (node (ref "C1") (pin "1") (pinfunction "1_1") (pintype "passive"))
      (node (ref "C10") (pin "1") (pinfunction "1_1") (pintype "passive"))
      (node (ref "C11") (pin "2") (pinfunction "2_2") (pintype "passive"))
      (node (ref "C12") (pin "1") (pinfunction "1_1") (pintype "passive"))
      (node (ref "C13") (pin "1") (pinfunction "1_1") (pintype "passive"))
      (node (ref "C14") (pin "1") (pinfunction "1_1") (pintype "passive"))
      (node (ref "C15") (pin "1") (pinfunction "1_1") (pintype "passive"))
      (node (ref "C16") (pin "1") (pinfunction "1_1") (pintype "passive"))
      (node (ref "C17") (pin "1") (pinfunction "1_1") (pintype "passive"))
      (node (ref "C18") (pin "1") (pinfunction "1_1") (pintype "passive"))
      (node (ref "C19") (pin "1") (pinfunction "1_1") (pintype "passive"))
      (node (ref "C2") (pin "1") (pinfunction "1_1") (pintype "passive"))
      (node (ref "C20") (pin "1") (pinfunction "1_1") (pintype "passive"))
      (node (ref "C3") (pin "1") (pinfunction "1_1") (pintype "passive"))
      (node (ref "C4") (pin "1") (pinfunction "1_1") (pintype "passive"))
      (node (ref "C5") (pin "1") (pinfunction "1_1") (pintype "passive"))
      (node (ref "C6") (pin "1") (pinfunction "1_1") (pintype "passive"))
      (node (ref "C7") (pin "1") (pinfunction "1_1") (pintype "passive"))
      (node (ref "C8") (pin "1") (pinfunction "1_1") (pintype "passive"))
      (node (ref "C9") (pin "1") (pinfunction "1_1") (pintype "passive"))
      (node (ref "H0") (pin "4") (pinfunction "4_4") (pintype "passive"))
      (node (ref "K0") (pin "2") (pinfunction "2_2") (pintype "passive"))
      (node (ref "L0") (pin "1") (pinfunction "GND1_1") (pintype "passive"))
      (node (ref "L0") (pin "12") (pinfunction "GND4_12") (pintype "passive"))
      (node (ref "L0") (pin "5") (pinfunction "GND2_5") (pintype "passive"))
      (node (ref "L0") (pin "6") (pinfunction "GND3_6") (pintype "passive"))
      (node (ref "LED1") (pin "2") (pinfunction "2_2") (pintype "passive"))
      (node (ref "LED2") (pin "2") (pinfunction "2_2") (pintype "passive"))
      (node (ref "P1") (pin "8") (pinfunction "8_8") (pintype "passive"))
      (node (ref "P7") (pin "3") (pinfunction "3_3") (pintype "passive"))
      (node (ref "P8") (pin "2") (pinfunction "-_2") (pintype "passive"))
      (node (ref "R11") (pin "1") (pinfunction "1_1") (pintype "passive"))
      (node (ref "R111") (pin "1") (pinfunction "1_1") (pintype "passive"))
      (node (ref "R13") (pin "2") (pinfunction "2_2") (pintype "passive"))
      (node (ref "R15") (pin "2") (pinfunction "2_2") (pintype "passive"))
      (node (ref "R16") (pin "1") (pinfunction "1_1") (pintype "passive"))
      (node (ref "R18") (pin "1") (pinfunction "1_1") (pintype "passive"))
      (node (ref "R2") (pin "2") (pinfunction "2_2") (pintype "passive"))
      (node (ref "R222") (pin "1") (pinfunction "1_1") (pintype "passive"))
      (node (ref "U0") (pin "23") (pinfunction "VSS_23") (pintype "passive"))
      (node (ref "U0") (pin "35") (pinfunction "VSS_35") (pintype "passive"))
      (node (ref "U0") (pin "47") (pinfunction "VSS_47") (pintype "passive"))
      (node (ref "U0") (pin "49") (pinfunction "EP_49") (pintype "passive"))
      (node (ref "U0") (pin "8") (pinfunction "VSSA/VREF+_8") (pintype "passive"))
      (node (ref "U1") (pin "24") (pinfunction "GND_24") (pintype "passive"))
      (node (ref "U2") (pin "2") (pinfunction "E_2") (pintype "passive"))
      (node (ref "U3") (pin "3") (pinfunction "GND_3") (pintype "passive"))
      (node (ref "U4") (pin "2") (pinfunction "GND_2") (pintype "passive"))
      (node (ref "U5") (pin "2") (pinfunction "SOURCE_2") (pintype "passive"))
      (node (ref "U6") (pin "1") (pinfunction "VSS_1") (pintype "passive"))
      (node (ref "U7") (pin "2") (pinfunction "GND_2") (pintype "passive"))
      (node (ref "U8") (pin "7") (pinfunction "R_7") (pintype "passive"))
      (node (ref "U8") (pin "8") (pinfunction "VSS_8") (pintype "passive"))
      (node (ref "U8") (pin "9") (pinfunction "PAD_9") (pintype "passive"))
      (node (ref "U9") (pin "2") (pinfunction "VSS_2") (pintype "passive"))
      (node (ref "USB0") (pin "A1B12") (pinfunction "GND_A1B12") (pintype "power_in"))
      (node (ref "USB0") (pin "B1A12") (pinfunction "GND_B1A12") (pintype "power_in"))
      (node (ref "X0") (pin "2") (pinfunction "GND_2") (pintype "passive"))
    )
    (net (code "47") (name "Net-(A0-D+)") (class "Default")
      (node (ref "A0") (pin "3") (pinfunction "D+_3") (pintype "passive"))
      (node (ref "R9") (pin "2") (pinfunction "2_2") (pintype "passive"))
    )
    (net (code "48") (name "Net-(A0-D_-)") (class "Default")
      (node (ref "A0") (pin "2") (pinfunction "D_-_2") (pintype "passive"))
      (node (ref "R10") (pin "2") (pinfunction "2_2") (pintype "passive"))
    )
    (net (code "49") (name "Net-(B0-power+)") (class "Default")
      (node (ref "B0") (pin "1") (pinfunction "power+_1") (pintype "passive"))
      (node (ref "P10") (pin "1") (pinfunction "1_1") (pintype "passive"))
    )
    (net (code "50") (name "Net-(B0-power-)") (class "Default")
      (node (ref "B0") (pin "2") (pinfunction "power-_2") (pintype "passive"))
      (node (ref "P11") (pin "2") (pinfunction "-_2") (pintype "passive"))
      (node (ref "U5") (pin "3") (pinfunction "DRAIN_3") (pintype "passive"))
    )
    (net (code "51") (name "Net-(LED 0-Pad1)") (class "Default")
      (node (ref "LED 0") (pin "1") (pinfunction "1_1") (pintype "passive"))
      (node (ref "R3") (pin "1") (pinfunction "1_1") (pintype "passive"))
    )
    (net (code "52") (name "Net-(LED1-Pad1)") (class "Default")
      (node (ref "LED1") (pin "1") (pinfunction "1_1") (pintype "passive"))
      (node (ref "R21") (pin "1") (pinfunction "1_1") (pintype "passive"))
    )
    (net (code "53") (name "Net-(LED2-Pad1)") (class "Default")
      (node (ref "LED2") (pin "1") (pinfunction "1_1") (pintype "passive"))
      (node (ref "R22") (pin "1") (pinfunction "1_1") (pintype "passive"))
    )
    (net (code "54") (name "Net-(P8-+)") (class "Default")
      (node (ref "P8") (pin "1") (pinfunction "+_1") (pintype "passive"))
      (node (ref "SW0") (pin "3") (pinfunction "3_3") (pintype "passive"))
    )
    (net (code "55") (name "Net-(P11-+)") (class "Default")
      (node (ref "P10") (pin "3") (pinfunction "3_3") (pintype "passive"))
      (node (ref "P11") (pin "1") (pinfunction "+_1") (pintype "passive"))
    )
    (net (code "56") (name "Net-(U0-VBAT)") (class "Default")
      (node (ref "U0") (pin "1") (pinfunction "VBAT_1") (pintype "passive"))
      (node (ref "VBAT") (pin "1") (pinfunction "1_1") (pintype "passive"))
    )
    (net (code "57") (name "Net-(U2-B)") (class "Default")
      (node (ref "R6") (pin "2") (pinfunction "2_2") (pintype "passive"))
      (node (ref "R7") (pin "1") (pinfunction "1_1") (pintype "passive"))
      (node (ref "U2") (pin "1") (pinfunction "B_1") (pintype "passive"))
    )
    (net (code "58") (name "Net-(U2-C)") (class "Default")
      (node (ref "R8") (pin "2") (pinfunction "2_2") (pintype "passive"))
      (node (ref "U2") (pin "3") (pinfunction "C_3") (pintype "passive"))
    )
    (net (code "59") (name "Net-(U3-V3)") (class "Default")
      (node (ref "C12") (pin "2") (pinfunction "2_2") (pintype "passive"))
      (node (ref "U3") (pin "10") (pinfunction "V3_10") (pintype "passive"))
    )
    (net (code "60") (name "Net-(U4-POR)") (class "Default")
      (node (ref "R11") (pin "2") (pinfunction "2_2") (pintype "passive"))
      (node (ref "U4") (pin "5") (pinfunction "POR_5") (pintype "passive"))
    )
    (net (code "61") (name "Net-(U4-VCC)") (class "Default")
      (node (ref "R12") (pin "2") (pinfunction "2_2") (pintype "passive"))
      (node (ref "U4") (pin "4") (pinfunction "VCC_4") (pintype "passive"))
    )
    (net (code "62") (name "Net-(U8-ADDR)") (class "Default")
      (node (ref "R18") (pin "2") (pinfunction "2_2") (pintype "passive"))
      (node (ref "U8") (pin "2") (pinfunction "ADDR_2") (pintype "passive"))
    )
    (net (code "63") (name "Net-(U9-KEY1)") (class "Default")
      (node (ref "C18") (pin "2") (pinfunction "2_2") (pintype "passive"))
      (node (ref "P9") (pin "1") (pinfunction "1_1") (pintype "passive"))
      (node (ref "U9") (pin "6") (pinfunction "KEY1_6") (pintype "passive"))
    )
    (net (code "64") (name "Net-(U9-KEY2)") (class "Default")
      (node (ref "C19") (pin "2") (pinfunction "2_2") (pintype "passive"))
      (node (ref "P9") (pin "2") (pinfunction "2_2") (pintype "passive"))
      (node (ref "U9") (pin "5") (pinfunction "KEY2_5") (pintype "passive"))
    )
    (net (code "65") (name "Net-(USB0-CC1)") (class "Default")
      (node (ref "R111") (pin "2") (pinfunction "2_2") (pintype "passive"))
      (node (ref "USB0") (pin "A5") (pinfunction "CC1_A5") (pintype "power_in"))
    )
    (net (code "66") (name "Net-(USB0-CC2)") (class "Default")
      (node (ref "R222") (pin "2") (pinfunction "2_2") (pintype "passive"))
      (node (ref "USB0") (pin "B5") (pinfunction "CC2_B5") (pintype "power_in"))
    )
    (net (code "67") (name "V2.5") (class "Default")
      (node (ref "C15") (pin "2") (pinfunction "2_2") (pintype "passive"))
      (node (ref "P4") (pin "8") (pinfunction "8_8") (pintype "passive"))
      (node (ref "POW-BEEOP") (pin "3") (pinfunction "3_3") (pintype "passive"))
      (node (ref "POW-BLUE") (pin "3") (pinfunction "3_3") (pintype "passive"))
      (node (ref "POW-CPU") (pin "3") (pinfunction "3_3") (pintype "passive"))
      (node (ref "POW-LED") (pin "3") (pinfunction "3_3") (pintype "passive"))
      (node (ref "POW-MPU") (pin "3") (pinfunction "3_3") (pintype "passive"))
      (node (ref "POW-SHT30") (pin "3") (pinfunction "3_3") (pintype "passive"))
      (node (ref "POW-TOUCH") (pin "3") (pinfunction "3_3") (pintype "passive"))
      (node (ref "R22") (pin "2") (pinfunction "2_2") (pintype "passive"))
      (node (ref "U6") (pin "2") (pinfunction "VOUT_2") (pintype "passive"))
    )
    (net (code "68") (name "VDD-BEEP") (class "Default")
      (node (ref "P10") (pin "2") (pinfunction "2_2") (pintype "passive"))
      (node (ref "POW-BEEOP") (pin "2") (pinfunction "2_2") (pintype "passive"))
    )
    (net (code "69") (name "VDD-BLUE") (class "Default")
      (node (ref "POW-BLUE") (pin "2") (pinfunction "2_2") (pintype "passive"))
      (node (ref "U1") (pin "1") (pinfunction "VCC_1") (pintype "passive"))
    )
    (net (code "70") (name "VDD-LED") (class "Default")
      (node (ref "L0") (pin "4") (pinfunction "VDD_4") (pintype "passive"))
      (node (ref "POW-LED") (pin "2") (pinfunction "2_2") (pintype "passive"))
      (node (ref "R6") (pin "1") (pinfunction "1_1") (pintype "passive"))
    )
    (net (code "71") (name "VDD-MCU") (class "Default")
      (node (ref "C10") (pin "2") (pinfunction "2_2") (pintype "passive"))
      (node (ref "C7") (pin "2") (pinfunction "2_2") (pintype "passive"))
      (node (ref "C8") (pin "2") (pinfunction "2_2") (pintype "passive"))
      (node (ref "C9") (pin "2") (pinfunction "2_2") (pintype "passive"))
      (node (ref "H0") (pin "3") (pinfunction "3_3") (pintype "passive"))
      (node (ref "POW-CPU") (pin "2") (pinfunction "2_2") (pintype "passive"))
      (node (ref "R1") (pin "2") (pinfunction "2_2") (pintype "passive"))
      (node (ref "R3") (pin "2") (pinfunction "2_2") (pintype "passive"))
      (node (ref "U0") (pin "24") (pinfunction "VDD_24") (pintype "passive"))
      (node (ref "U0") (pin "36") (pinfunction "VDD_36") (pintype "passive"))
      (node (ref "U0") (pin "48") (pinfunction "VDD_48") (pintype "passive"))
      (node (ref "U0") (pin "9") (pinfunction "VDDA/VREF+_9") (pintype "passive"))
      (node (ref "VBAT") (pin "2") (pinfunction "2_2") (pintype "passive"))
    )
    (net (code "72") (name "VDD-MPU") (class "Default")
      (node (ref "P7") (pin "1") (pinfunction "1_1") (pintype "passive"))
      (node (ref "P7") (pin "2") (pinfunction "2_2") (pintype "passive"))
      (node (ref "POW-MPU") (pin "2") (pinfunction "2_2") (pintype "passive"))
    )
    (net (code "73") (name "VDD-SHT30") (class "Default")
      (node (ref "C20") (pin "2") (pinfunction "2_2") (pintype "passive"))
      (node (ref "POW-SHT30") (pin "2") (pinfunction "2_2") (pintype "passive"))
      (node (ref "R19") (pin "1") (pinfunction "1_1") (pintype "passive"))
      (node (ref "R20") (pin "1") (pinfunction "1_1") (pintype "passive"))
      (node (ref "U8") (pin "5") (pinfunction "VDD_5") (pintype "passive"))
    )
    (net (code "74") (name "VDD-TOUCH") (class "Default")
      (node (ref "C17") (pin "2") (pinfunction "2_2") (pintype "passive"))
      (node (ref "POW-TOUCH") (pin "2") (pinfunction "2_2") (pintype "passive"))
      (node (ref "U9") (pin "1") (pinfunction "VDD_1") (pintype "passive"))
    )
    (net (code "75") (name "unconnected-(A0-ID-Pad4)") (class "Default")
      (node (ref "A0") (pin "4") (pinfunction "ID_4") (pintype "passive+no_connect"))
    )
    (net (code "76") (name "unconnected-(A0-Pad6)") (class "Default")
      (node (ref "A0") (pin "6") (pinfunction "6_6") (pintype "passive"))
    )
    (net (code "77") (name "unconnected-(A0-Pad7)") (class "Default")
      (node (ref "A0") (pin "7") (pinfunction "7_7") (pintype "passive"))
    )
    (net (code "78") (name "unconnected-(A0-Pad8)") (class "Default")
      (node (ref "A0") (pin "8") (pinfunction "8_8") (pintype "passive"))
    )
    (net (code "79") (name "unconnected-(A0-Pad9)") (class "Default")
      (node (ref "A0") (pin "9") (pinfunction "9_9") (pintype "passive"))
    )
    (net (code "80") (name "unconnected-(SW0-Pad1)") (class "Default")
      (node (ref "SW0") (pin "1") (pinfunction "1_1") (pintype "passive+no_connect"))
    )
    (net (code "81") (name "unconnected-(U1-ADC-Pad3)") (class "Default")
      (node (ref "U1") (pin "3") (pinfunction "ADC_3") (pintype "passive+no_connect"))
    )
    (net (code "82") (name "unconnected-(U1-ALED-Pad17)") (class "Default")
      (node (ref "U1") (pin "17") (pinfunction "ALED_17") (pintype "passive+no_connect"))
    )
    (net (code "83") (name "unconnected-(U1-IO1-Pad9)") (class "Default")
      (node (ref "U1") (pin "9") (pinfunction "IO1_9") (pintype "passive+no_connect"))
    )
    (net (code "84") (name "unconnected-(U1-IO2-Pad10)") (class "Default")
      (node (ref "U1") (pin "10") (pinfunction "IO2_10") (pintype "passive+no_connect"))
    )
    (net (code "85") (name "unconnected-(U1-IO3-Pad13)") (class "Default")
      (node (ref "U1") (pin "13") (pinfunction "IO3_13") (pintype "passive+no_connect"))
    )
    (net (code "86") (name "unconnected-(U1-IO4-Pad8)") (class "Default")
      (node (ref "U1") (pin "8") (pinfunction "IO4_8") (pintype "passive+no_connect"))
    )
    (net (code "87") (name "unconnected-(U1-IO5-Pad7)") (class "Default")
      (node (ref "U1") (pin "7") (pinfunction "IO5_7") (pintype "passive+no_connect"))
    )
    (net (code "88") (name "unconnected-(U1-IO6-Pad5)") (class "Default")
      (node (ref "U1") (pin "5") (pinfunction "IO6_5") (pintype "passive+no_connect"))
    )
    (net (code "89") (name "unconnected-(U1-IO7-Pad14)") (class "Default")
      (node (ref "U1") (pin "14") (pinfunction "IO7_14") (pintype "passive+no_connect"))
    )
    (net (code "90") (name "unconnected-(U1-IO8-Pad15)") (class "Default")
      (node (ref "U1") (pin "15") (pinfunction "IO8_15") (pintype "passive+no_connect"))
    )
    (net (code "91") (name "unconnected-(U1-IO9-Pad16)") (class "Default")
      (node (ref "U1") (pin "16") (pinfunction "IO9_16") (pintype "passive+no_connect"))
    )
    (net (code "92") (name "unconnected-(U1-NULL-Pad2)") (class "Default")
      (node (ref "U1") (pin "2") (pinfunction "NULL_2") (pintype "passive+no_connect"))
    )
    (net (code "93") (name "unconnected-(U1-NULL-Pad4)") (class "Default")
      (node (ref "U1") (pin "4") (pinfunction "NULL_4") (pintype "passive+no_connect"))
    )
    (net (code "94") (name "unconnected-(U1-NULL-Pad11)") (class "Default")
      (node (ref "U1") (pin "11") (pinfunction "NULL_11") (pintype "passive+no_connect"))
    )
    (net (code "95") (name "unconnected-(U1-NULL-Pad12)") (class "Default")
      (node (ref "U1") (pin "12") (pinfunction "NULL_12") (pintype "passive+no_connect"))
    )
    (net (code "96") (name "unconnected-(U3-CTS#-Pad5)") (class "Default")
      (node (ref "U3") (pin "5") (pinfunction "CTS#_5") (pintype "passive+no_connect"))
    )
    (net (code "97") (name "unconnected-(U3-RTS#-Pad4)") (class "Default")
      (node (ref "U3") (pin "4") (pinfunction "RTS#_4") (pintype "passive+no_connect"))
    )
    (net (code "98") (name "unconnected-(U3-TNOW-Pad1)") (class "Default")
      (node (ref "U3") (pin "1") (pinfunction "TNOW_1") (pintype "passive+no_connect"))
    )
    (net (code "99") (name "unconnected-(U7-NC-Pad4)") (class "Default")
      (node (ref "U7") (pin "4") (pinfunction "NC_4") (pintype "passive+no_connect"))
    )
    (net (code "100") (name "unconnected-(U8-ALE-Pad3)") (class "Default")
      (node (ref "U8") (pin "3") (pinfunction "ALE_3") (pintype "passive+no_connect"))
    )
    (net (code "101") (name "unconnected-(U8-RES-Pad6)") (class "Default")
      (node (ref "U8") (pin "6") (pinfunction "RES_6") (pintype "passive+no_connect"))
    )
    (net (code "102") (name "unconnected-(USB0-SBU1-PadA8)") (class "Default")
      (node (ref "USB0") (pin "A8") (pinfunction "SBU1_A8") (pintype "power_in+no_connect"))
    )
    (net (code "103") (name "unconnected-(USB0-SBU2-PadB8)") (class "Default")
      (node (ref "USB0") (pin "B8") (pinfunction "SBU2_B8") (pintype "power_in+no_connect"))
    )
    (net (code "104") (name "unconnected-(USB0-SHELL-Pad1)") (class "Default")
      (node (ref "USB0") (pin "1") (pinfunction "SHELL_1") (pintype "power_in+no_connect"))
    )
    (net (code "105") (name "unconnected-(USB0-SHELL-Pad2)") (class "Default")
      (node (ref "USB0") (pin "2") (pinfunction "SHELL_2") (pintype "power_in+no_connect"))
    )
    (net (code "106") (name "unconnected-(USB0-SHELL-Pad3)") (class "Default")
      (node (ref "USB0") (pin "3") (pinfunction "SHELL_3") (pintype "power_in+no_connect"))
    )
    (net (code "107") (name "unconnected-(USB0-SHELL-Pad4)") (class "Default")
      (node (ref "USB0") (pin "4") (pinfunction "SHELL_4") (pintype "power_in+no_connect"))
    )
  )
)
